# Current_Voltage_measure.net
KiCad netlist of a schematic drawn in Altium Designer
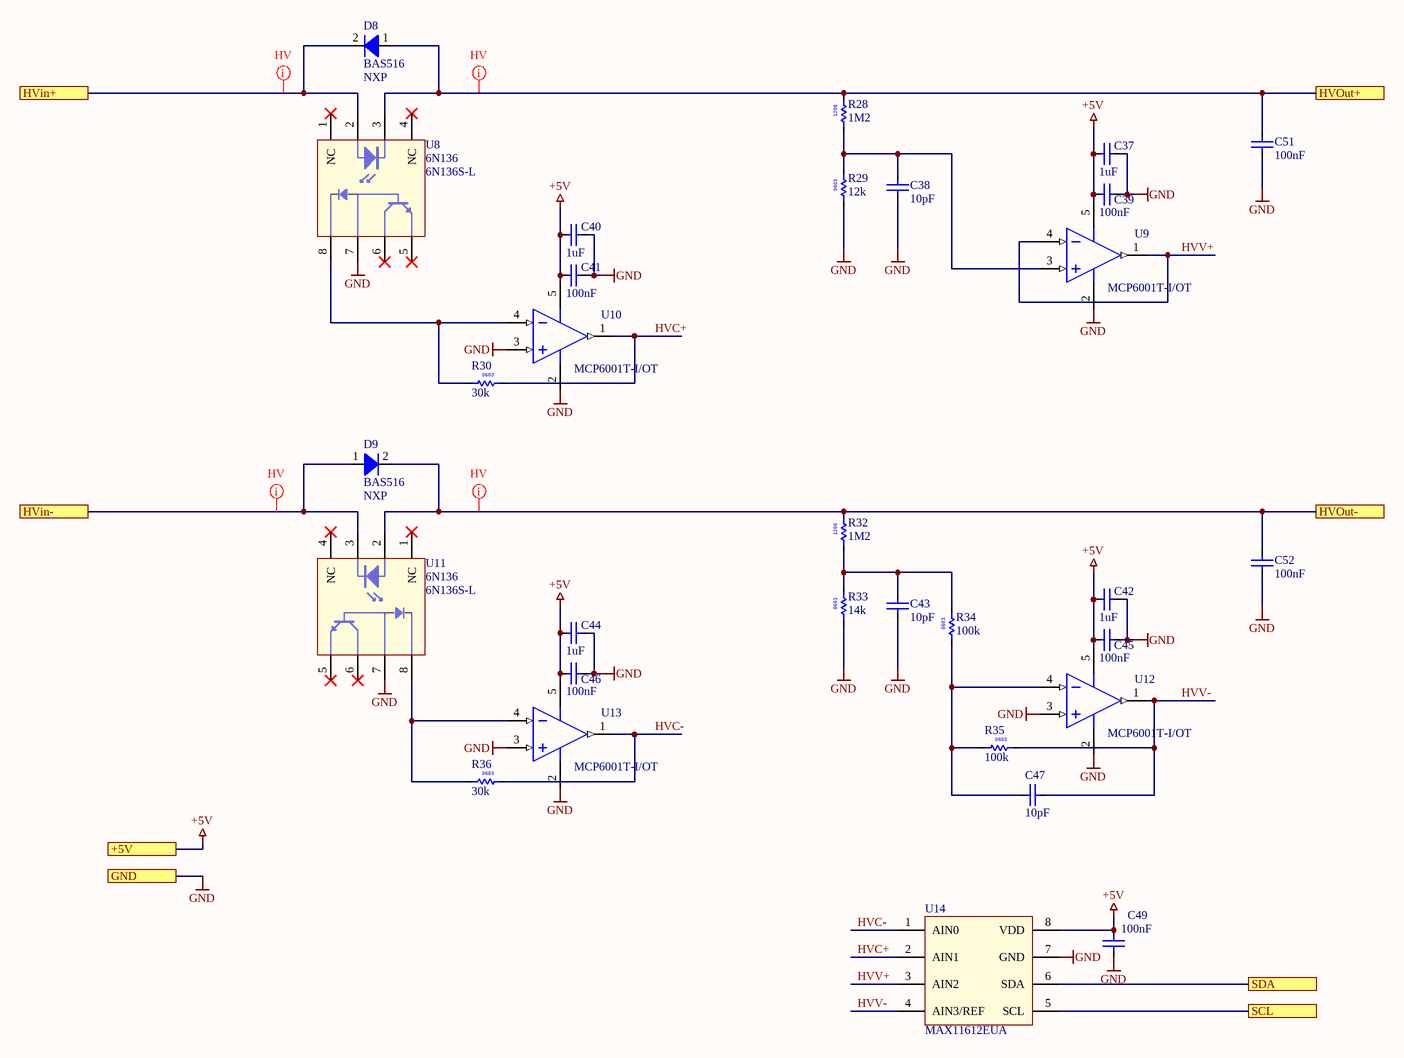
[diagram p0: Current_Voltage_measure.SchDoc]

(export (version "E")
  (design (tool "Eeschema 10.0.6"))
  (components
    (comp (ref "C37")
      (value "1uF")
      (footprint "CAPC2012N")
      (description "MLCC, 0805, X5R, 16V, 1uF")
      (fields (field (name "PART NUMBER") "C0000037") (field (name "VOLTAGE") "16"))
      (libsource (lib "KTU_DB") (part "C_SM"))
    )
    (comp (ref "C38")
      (value "10pF")
      (footprint "CAPC1608N")
      (description "MLCC, 0603, NP0, 50V, 10PF")
      (fields (field (name "PART NUMBER") "C0000042") (field (name "VOLTAGE") "100"))
      (libsource (lib "KTU_DB") (part "C_SM"))
    )
    (comp (ref "C39")
      (value "100nF")
      (footprint "C0603V")
      (description "MLCC, 0.1uF 16V 10% X7R 0603")
      (fields (field (name "PART NUMBER") "C0000005") (field (name "VOLTAGE") "16"))
      (libsource (lib "KTU_DB") (part "C_SM"))
    )
    (comp (ref "C40")
      (value "1uF")
      (footprint "CAPC2012N")
      (description "MLCC, 0805, X5R, 16V, 1uF")
      (fields (field (name "PART NUMBER") "C0000037") (field (name "VOLTAGE") "16"))
      (libsource (lib "KTU_DB") (part "C_SM"))
    )
    (comp (ref "C41")
      (value "100nF")
      (footprint "C0603V")
      (description "MLCC, 0.1uF 16V 10% X7R 0603")
      (fields (field (name "PART NUMBER") "C0000005") (field (name "VOLTAGE") "16"))
      (libsource (lib "KTU_DB") (part "C_SM"))
    )
    (comp (ref "C42")
      (value "1uF")
      (footprint "CAPC2012N")
      (description "MLCC, 0805, X5R, 16V, 1uF")
      (fields (field (name "PART NUMBER") "C0000037") (field (name "VOLTAGE") "16"))
      (libsource (lib "KTU_DB") (part "C_SM"))
    )
    (comp (ref "C43")
      (value "10pF")
      (footprint "CAPC1608N")
      (description "MLCC, 0603, NP0, 50V, 10PF")
      (fields (field (name "PART NUMBER") "C0000042") (field (name "VOLTAGE") "100"))
      (libsource (lib "KTU_DB") (part "C_SM"))
    )
    (comp (ref "C44")
      (value "1uF")
      (footprint "CAPC2012N")
      (description "MLCC, 0805, X5R, 16V, 1uF")
      (fields (field (name "PART NUMBER") "C0000037") (field (name "VOLTAGE") "16"))
      (libsource (lib "KTU_DB") (part "C_SM"))
    )
    (comp (ref "C45")
      (value "100nF")
      (footprint "C0603V")
      (description "MLCC, 0.1uF 16V 10% X7R 0603")
      (fields (field (name "PART NUMBER") "C0000005") (field (name "VOLTAGE") "16"))
      (libsource (lib "KTU_DB") (part "C_SM"))
    )
    (comp (ref "C46")
      (value "100nF")
      (footprint "C0603V")
      (description "MLCC, 0.1uF 16V 10% X7R 0603")
      (fields (field (name "PART NUMBER") "C0000005") (field (name "VOLTAGE") "16"))
      (libsource (lib "KTU_DB") (part "C_SM"))
    )
    (comp (ref "C47")
      (value "10pF")
      (footprint "CAPC1608N")
      (description "MLCC, 0603, NP0, 50V, 10PF")
      (fields (field (name "PART NUMBER") "C0000042") (field (name "VOLTAGE") "100"))
      (libsource (lib "KTU_DB") (part "C_SM"))
    )
    (comp (ref "C49")
      (value "100nF")
      (footprint "C0603V")
      (description "MLCC, 0.1uF 16V 10% X7R 0603")
      (fields (field (name "PART NUMBER") "C0000005") (field (name "VOLTAGE") "16"))
      (libsource (lib "KTU_DB") (part "C_SM"))
    )
    (comp (ref "C51")
      (value "100nF")
      (footprint "C1808")
      (description "MLCC, X7R, 100NF, 630V, 1808")
      (fields (field (name "PART NUMBER") "C0000111") (field (name "VOLTAGE") "630"))
      (libsource (lib "KTU_DB") (part "C_SM"))
    )
    (comp (ref "C52")
      (value "100nF")
      (footprint "C1808")
      (description "MLCC, X7R, 100NF, 630V, 1808")
      (fields (field (name "PART NUMBER") "C0000111") (field (name "VOLTAGE") "630"))
      (libsource (lib "KTU_DB") (part "C_SM"))
    )
    (comp (ref "D8")
      (value "BAS516")
      (footprint "SOD523")
      (description "DIODE, SWITCHING, SOD-523")
      (fields (field (name "PART NUMBER") "D0000081") (field (name "MANUFACTURER") "NXP"))
      (libsource (lib "KTU_DB") (part "Diode"))
    )
    (comp (ref "D9")
      (value "BAS516")
      (footprint "SOD523")
      (description "DIODE, SWITCHING, SOD-523")
      (fields (field (name "PART NUMBER") "D0000081") (field (name "MANUFACTURER") "NXP"))
      (libsource (lib "KTU_DB") (part "Diode"))
    )
    (comp (ref "R28")
      (value "1M2")
      (footprint "RESC3216N")
      (description "Res, 1M 0.25W, 1% 1206")
      (fields (field (name "TOLERANCE") "±1%") (field (name "POWER") "0.25W"))
      (libsource (lib "KTU_DB") (part "R1206"))
    )
    (comp (ref "R29")
      (value "12k")
      (footprint "RESC1608X50N")
      (description "Res, 12K, 0603 (1608 metric), ±1%, 100mW, 75V")
      (fields (field (name "TOLERANCE") "±1%") (field (name "POWER") "100mW"))
      (libsource (lib "KTU_DB") (part "R0603"))
    )
    (comp (ref "R30")
      (value "30k")
      (footprint "RESC1608N")
      (description "30K 5% 0603 1/10W")
      (fields (field (name "TOLERANCE") "±5%") (field (name "POWER") "1/10W"))
      (libsource (lib "KTU_DB") (part "R0603"))
    )
    (comp (ref "R32")
      (value "1M2")
      (footprint "RESC3216N")
      (description "Res, 1M 0.25W, 1% 1206")
      (fields (field (name "TOLERANCE") "±1%") (field (name "POWER") "0.25W"))
      (libsource (lib "KTU_DB") (part "R1206"))
    )
    (comp (ref "R33")
      (value "14k")
      (footprint "RESC1608X50N")
      (description "Res, 14K, 0603 (1608 metric), ±1%, 100mW, 75V")
      (fields (field (name "TOLERANCE") "±1%") (field (name "POWER") "100mW"))
      (libsource (lib "KTU_DB") (part "R0603"))
    )
    (comp (ref "R34")
      (value "100k")
      (footprint "RESC1608X50N")
      (description "Res, 100K, 0603 (1608 metric), ±1%, 100mW, 75V")
      (fields (field (name "TOLERANCE") "±1%") (field (name "POWER") "100mW"))
      (libsource (lib "KTU_DB") (part "R0603"))
    )
    (comp (ref "R35")
      (value "100k")
      (footprint "RESC1608X50N")
      (description "Res, 100K, 0603 (1608 metric), ±1%, 100mW, 75V")
      (fields (field (name "TOLERANCE") "±1%") (field (name "POWER") "100mW"))
      (libsource (lib "KTU_DB") (part "R0603"))
    )
    (comp (ref "R36")
      (value "30k")
      (footprint "RESC1608N")
      (description "30K 5% 0603 1/10W")
      (fields (field (name "TOLERANCE") "±5%") (field (name "POWER") "1/10W"))
      (libsource (lib "KTU_DB") (part "R0603"))
    )
    (comp (ref "U8")
      (value "6N136")
      (footprint "SMP-8")
      (description "6N136.SDM  Optocoupler, Transistor Output, 1 Channel, Surface Mount DIP, 8 Pins, 50 mA, 5 kV, 19 %")
      (fields (field (name "SUPPLIER PART NUMBER 1") "6N136S-L"))
      (libsource (lib "") (part "6N136_1"))
    )
    (comp (ref "U9")
      (value "MCP6001T-I/OT")
      (footprint "SO-G5/X.45")
      (libsource (lib "D_klase") (part "MCP6001T-I/OT"))
    )
    (comp (ref "U10")
      (value "MCP6001T-I/OT")
      (footprint "SO-G5/X.45")
      (libsource (lib "D_klase") (part "MCP6001T-I/OT"))
    )
    (comp (ref "U11")
      (value "6N136")
      (footprint "SMP-8")
      (description "6N136.SDM  Optocoupler, Transistor Output, 1 Channel, Surface Mount DIP, 8 Pins, 50 mA, 5 kV, 19 %")
      (fields (field (name "SUPPLIER PART NUMBER 1") "6N136S-L"))
      (libsource (lib "D_klase") (part "6N136"))
    )
    (comp (ref "U12")
      (value "MCP6001T-I/OT")
      (footprint "SO-G5/X.45")
      (libsource (lib "D_klase") (part "MCP6001T-I/OT"))
    )
    (comp (ref "U13")
      (value "MCP6001T-I/OT")
      (footprint "SO-G5/X.45")
      (libsource (lib "D_klase") (part "MCP6001T-I/OT"))
    )
    (comp (ref "U14")
      (value "MAX11612EUA")
      (footprint "uMAX-8")
      (libsource (lib "D_klase") (part "MAX11612EUA"))
    )
  )
  (nets
    (net (code "1") (name "+5V") (class "Default")
      (node (ref "C37") (pin "1") (pinfunction "1_1") (pintype "passive"))
      (node (ref "C39") (pin "2") (pinfunction "2_2") (pintype "passive"))
      (node (ref "C40") (pin "1") (pinfunction "1_1") (pintype "passive"))
      (node (ref "C41") (pin "2") (pinfunction "2_2") (pintype "passive"))
      (node (ref "C42") (pin "1") (pinfunction "1_1") (pintype "passive"))
      (node (ref "C44") (pin "1") (pinfunction "1_1") (pintype "passive"))
      (node (ref "C45") (pin "2") (pinfunction "2_2") (pintype "passive"))
      (node (ref "C46") (pin "2") (pinfunction "2_2") (pintype "passive"))
      (node (ref "C49") (pin "1") (pinfunction "1_1") (pintype "passive"))
      (node (ref "U10") (pin "5") (pinfunction "V+_5") (pintype "power_in"))
      (node (ref "U12") (pin "5") (pinfunction "V+_5") (pintype "power_in"))
      (node (ref "U13") (pin "5") (pinfunction "V+_5") (pintype "power_in"))
      (node (ref "U14") (pin "8") (pinfunction "VDD_8") (pintype "passive"))
      (node (ref "U9") (pin "5") (pinfunction "V+_5") (pintype "power_in"))
    )
    (net (code "2") (name "/HVC+") (class "Default")
      (node (ref "R30") (pin "2") (pinfunction "2_2") (pintype "passive"))
      (node (ref "U10") (pin "1") (pinfunction "OUT_1") (pintype "output"))
      (node (ref "U14") (pin "2") (pinfunction "AIN1_2") (pintype "passive"))
    )
    (net (code "3") (name "/HVC-") (class "Default")
      (node (ref "R36") (pin "2") (pinfunction "2_2") (pintype "passive"))
      (node (ref "U13") (pin "1") (pinfunction "OUT_1") (pintype "output"))
      (node (ref "U14") (pin "1") (pinfunction "AIN0_1") (pintype "passive"))
    )
    (net (code "4") (name "/HVOut+") (class "Default")
      (node (ref "C51") (pin "2") (pinfunction "2_2") (pintype "passive"))
      (node (ref "D8") (pin "1") (pinfunction "anode_1") (pintype "passive"))
      (node (ref "R28") (pin "2") (pinfunction "2_2") (pintype "passive"))
      (node (ref "U8") (pin "3") (pinfunction "C_3") (pintype "passive"))
    )
    (net (code "5") (name "/HVOut-") (class "Default")
      (node (ref "C52") (pin "2") (pinfunction "2_2") (pintype "passive"))
      (node (ref "D9") (pin "2") (pinfunction "cathode_2") (pintype "passive"))
      (node (ref "R32") (pin "2") (pinfunction "2_2") (pintype "passive"))
      (node (ref "U11") (pin "2") (pinfunction "A_2") (pintype "passive"))
    )
    (net (code "6") (name "/HVV+") (class "Default")
      (node (ref "U14") (pin "3") (pinfunction "AIN2_3") (pintype "passive"))
      (node (ref "U9") (pin "1") (pinfunction "OUT_1") (pintype "output"))
      (node (ref "U9") (pin "4") (pinfunction "IN-_4") (pintype "input"))
    )
    (net (code "7") (name "/HVV-") (class "Default")
      (node (ref "C47") (pin "1") (pinfunction "1_1") (pintype "passive"))
      (node (ref "R35") (pin "2") (pinfunction "2_2") (pintype "passive"))
      (node (ref "U12") (pin "1") (pinfunction "OUT_1") (pintype "output"))
      (node (ref "U14") (pin "4") (pinfunction "AIN3/REF_4") (pintype "passive"))
    )
    (net (code "8") (name "/HVin+") (class "Default")
      (node (ref "D8") (pin "2") (pinfunction "cathode_2") (pintype "passive"))
      (node (ref "U8") (pin "2") (pinfunction "A_2") (pintype "passive"))
    )
    (net (code "9") (name "/HVin-") (class "Default")
      (node (ref "D9") (pin "1") (pinfunction "anode_1") (pintype "passive"))
      (node (ref "U11") (pin "3") (pinfunction "C_3") (pintype "passive"))
    )
    (net (code "10") (name "/SCL") (class "Default")
      (node (ref "U14") (pin "5") (pinfunction "SCL_5") (pintype "passive"))
    )
    (net (code "11") (name "/SDA") (class "Default")
      (node (ref "U14") (pin "6") (pinfunction "SDA_6") (pintype "passive"))
    )
    (net (code "12") (name "GND") (class "Default")
      (node (ref "C37") (pin "2") (pinfunction "2_2") (pintype "passive"))
      (node (ref "C38") (pin "1") (pinfunction "1_1") (pintype "passive"))
      (node (ref "C39") (pin "1") (pinfunction "1_1") (pintype "passive"))
      (node (ref "C40") (pin "2") (pinfunction "2_2") (pintype "passive"))
      (node (ref "C41") (pin "1") (pinfunction "1_1") (pintype "passive"))
      (node (ref "C42") (pin "2") (pinfunction "2_2") (pintype "passive"))
      (node (ref "C43") (pin "1") (pinfunction "1_1") (pintype "passive"))
      (node (ref "C44") (pin "2") (pinfunction "2_2") (pintype "passive"))
      (node (ref "C45") (pin "1") (pinfunction "1_1") (pintype "passive"))
      (node (ref "C46") (pin "1") (pinfunction "1_1") (pintype "passive"))
      (node (ref "C49") (pin "2") (pinfunction "2_2") (pintype "passive"))
      (node (ref "C51") (pin "1") (pinfunction "1_1") (pintype "passive"))
      (node (ref "C52") (pin "1") (pinfunction "1_1") (pintype "passive"))
      (node (ref "R29") (pin "1") (pinfunction "1_1") (pintype "passive"))
      (node (ref "R33") (pin "1") (pinfunction "1_1") (pintype "passive"))
      (node (ref "U10") (pin "2") (pinfunction "V-_2") (pintype "power_in"))
      (node (ref "U10") (pin "3") (pinfunction "IN+_3") (pintype "input"))
      (node (ref "U11") (pin "7") (pinfunction "Vb_7") (pintype "passive"))
      (node (ref "U12") (pin "2") (pinfunction "V-_2") (pintype "power_in"))
      (node (ref "U12") (pin "3") (pinfunction "IN+_3") (pintype "input"))
      (node (ref "U13") (pin "2") (pinfunction "V-_2") (pintype "power_in"))
      (node (ref "U13") (pin "3") (pinfunction "IN+_3") (pintype "input"))
      (node (ref "U14") (pin "7") (pinfunction "GND_7") (pintype "passive"))
      (node (ref "U8") (pin "7") (pinfunction "Vb_7") (pintype "passive"))
      (node (ref "U9") (pin "2") (pinfunction "V-_2") (pintype "power_in"))
    )
    (net (code "13") (name "Net-(C43-Pad2)") (class "Default")
      (node (ref "C43") (pin "2") (pinfunction "2_2") (pintype "passive"))
      (node (ref "R32") (pin "1") (pinfunction "1_1") (pintype "passive"))
      (node (ref "R33") (pin "2") (pinfunction "2_2") (pintype "passive"))
      (node (ref "R34") (pin "2") (pinfunction "2_2") (pintype "passive"))
    )
    (net (code "14") (name "Net-(U9-IN+)") (class "Default")
      (node (ref "C38") (pin "2") (pinfunction "2_2") (pintype "passive"))
      (node (ref "R28") (pin "1") (pinfunction "1_1") (pintype "passive"))
      (node (ref "R29") (pin "2") (pinfunction "2_2") (pintype "passive"))
      (node (ref "U9") (pin "3") (pinfunction "IN+_3") (pintype "input"))
    )
    (net (code "15") (name "Net-(U10-IN-)") (class "Default")
      (node (ref "R30") (pin "1") (pinfunction "1_1") (pintype "passive"))
      (node (ref "U10") (pin "4") (pinfunction "IN-_4") (pintype "input"))
      (node (ref "U8") (pin "8") (pinfunction "Vcc_8") (pintype "passive"))
    )
    (net (code "16") (name "Net-(U11-Vcc)") (class "Default")
      (node (ref "R36") (pin "1") (pinfunction "1_1") (pintype "passive"))
      (node (ref "U11") (pin "8") (pinfunction "Vcc_8") (pintype "passive"))
      (node (ref "U13") (pin "4") (pinfunction "IN-_4") (pintype "input"))
    )
    (net (code "17") (name "Net-(U12-IN-)") (class "Default")
      (node (ref "C47") (pin "2") (pinfunction "2_2") (pintype "passive"))
      (node (ref "R34") (pin "1") (pinfunction "1_1") (pintype "passive"))
      (node (ref "R35") (pin "1") (pinfunction "1_1") (pintype "passive"))
      (node (ref "U12") (pin "4") (pinfunction "IN-_4") (pintype "input"))
    )
    (net (code "18") (name "unconnected-(U8-GND-Pad5)") (class "Default")
      (node (ref "U8") (pin "5") (pinfunction "GND_5") (pintype "passive+no_connect"))
    )
    (net (code "19") (name "unconnected-(U8-NC-Pad1)") (class "Default")
      (node (ref "U8") (pin "1") (pinfunction "NC_1") (pintype "passive+no_connect"))
    )
    (net (code "20") (name "unconnected-(U8-NC-Pad4)") (class "Default")
      (node (ref "U8") (pin "4") (pinfunction "NC_4") (pintype "passive+no_connect"))
    )
    (net (code "21") (name "unconnected-(U8-Vo-Pad6)") (class "Default")
      (node (ref "U8") (pin "6") (pinfunction "Vo_6") (pintype "passive+no_connect"))
    )
    (net (code "22") (name "unconnected-(U11-GND-Pad5)") (class "Default")
      (node (ref "U11") (pin "5") (pinfunction "GND_5") (pintype "passive+no_connect"))
    )
    (net (code "23") (name "unconnected-(U11-NC-Pad1)") (class "Default")
      (node (ref "U11") (pin "1") (pinfunction "NC_1") (pintype "passive+no_connect"))
    )
    (net (code "24") (name "unconnected-(U11-NC-Pad4)") (class "Default")
      (node (ref "U11") (pin "4") (pinfunction "NC_4") (pintype "passive+no_connect"))
    )
    (net (code "25") (name "unconnected-(U11-Vo-Pad6)") (class "Default")
      (node (ref "U11") (pin "6") (pinfunction "Vo_6") (pintype "passive+no_connect"))
    )
  )
)
